# Top_Level.net
KiCad netlist of a schematic drawn in Altium Designer
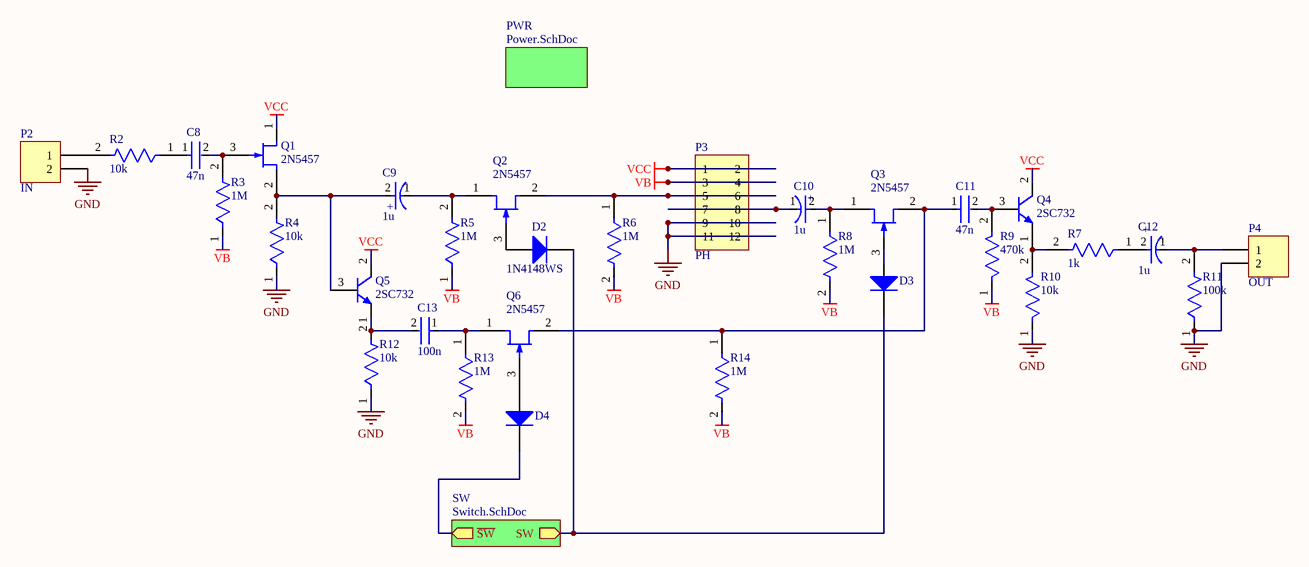
[diagram p0: Top_Level.SchDoc]

(export (version "E")
  (design (tool "Eeschema 10.0.6"))
  (components
    (comp (ref "C8")
      (value "47n")
      (footprint "FP-CL10-IPC_A")
      (description "Cap Ceramic 1nF 50V C0G ±5% Pad SMD 0603 +125°C T/R")
      (fields (field (name "VOLTAGE") "50V") (field (name "TOLERANCE") "5%"))
      (libsource (lib "Altium Content Vault") (part "b4654b650e69147ec39a6b967a45e02"))
    )
    (comp (ref "C9")
      (value "1u")
      (footprint "FP-TAJA-MFG")
      (description "10uF 16V  ±10% 3Ω 1206  SMD Tantalum Capacitor")
      (fields (field (name "VOLTAGE") "16V") (field (name "TOLERANCE") "10%"))
      (libsource (lib "Altium Content Vault") (part "203bc49f2ac43e59fd269a8c329ed05"))
    )
    (comp (ref "C10")
      (value "1u")
      (footprint "FP-TAJA-MFG")
      (description "10uF 16V  ±10% 3Ω 1206  SMD Tantalum Capacitor")
      (fields (field (name "VOLTAGE") "16V") (field (name "TOLERANCE") "10%"))
      (libsource (lib "Altium Content Vault") (part "203bc49f2ac43e59fd269a8c329ed05"))
    )
    (comp (ref "C11")
      (value "47n")
      (footprint "FP-CL10-IPC_A")
      (description "Cap Ceramic 1nF 50V C0G ±5% Pad SMD 0603 +125°C T/R")
      (fields (field (name "VOLTAGE") "50V") (field (name "TOLERANCE") "5%"))
      (libsource (lib "Altium Content Vault") (part "b4654b650e69147ec39a6b967a45e02"))
    )
    (comp (ref "C12")
      (value "1u")
      (footprint "FP-TAJA-MFG")
      (description "10uF 16V  ±10% 3Ω 1206  SMD Tantalum Capacitor")
      (fields (field (name "VOLTAGE") "16V") (field (name "TOLERANCE") "10%"))
      (libsource (lib "Altium Content Vault") (part "203bc49f2ac43e59fd269a8c329ed05"))
    )
    (comp (ref "C13")
      (value "100n")
      (footprint "FP-CL10-IPC_A")
      (description "Cap Ceramic 1nF 50V C0G ±5% Pad SMD 0603 +125°C T/R")
      (fields (field (name "VOLTAGE") "50V") (field (name "TOLERANCE") "5%"))
      (libsource (lib "Altium Content Vault") (part "b4654b650e69147ec39a6b967a45e02"))
    )
    (comp (ref "D2")
      (value "1N4148WS")
      (footprint "DIOD-SOD323-2-A_V")
      (description "Fast Switching Diode, 75 V, 0.3 A, -65 to 150 degC, 2-Pin SOD323, RoHS, Tape and Reel")
      (libsource (lib "Altium Content Vault") (part "D-AK-2"))
    )
    (comp (ref "D3")
      (value "1N4148WS")
      (footprint "DIOD-SOD323-2-A_V")
      (description "Fast Switching Diode, 75 V, 0.3 A, -65 to 150 degC, 2-Pin SOD323, RoHS, Tape and Reel")
      (libsource (lib "Altium Content Vault") (part "D-AK-2"))
    )
    (comp (ref "D4")
      (value "1N4148WS")
      (footprint "DIOD-SOD323-2-A_V")
      (description "Fast Switching Diode, 75 V, 0.3 A, -65 to 150 degC, 2-Pin SOD323, RoHS, Tape and Reel")
      (libsource (lib "Altium Content Vault") (part "D-AK-2"))
    )
    (comp (ref "P2")
      (value "IN")
      (footprint "HDR1X2")
      (description "Header, 2-Pin")
      (fields (field (name "PUBLISHER") "Altium Limited"))
      (libsource (lib "Miscellaneous Connectors") (part "Header 2"))
    )
    (comp (ref "P3")
      (value "PH")
      (footprint "HDR2X6")
      (description "Header, 6-Pin, Dual row")
      (fields (field (name "PUBLISHER") "Altium Limited"))
      (libsource (lib "Miscellaneous Connectors") (part "Header 6X2"))
    )
    (comp (ref "P4")
      (value "OUT")
      (footprint "HDR1X2")
      (description "Header, 2-Pin")
      (fields (field (name "PUBLISHER") "Altium Limited"))
      (libsource (lib "") (part "Header 2_1"))
    )
    (comp (ref "Q1") (value "2N5457") (footprint "TO-92") (libsource (lib "TH_Symbols") (part "JFET_NPN")))
    (comp (ref "Q2") (value "2N5457") (footprint "TO-92") (libsource (lib "TH_Symbols") (part "JFET_NPN")))
    (comp (ref "Q3") (value "2N5457") (footprint "TO-92") (libsource (lib "TH_Symbols") (part "JFET_NPN")))
    (comp (ref "Q4") (value "2SC732") (footprint "TO-92") (libsource (lib "TH_Symbols") (part "BJT_NPN")))
    (comp (ref "Q5") (value "2SC732") (footprint "TO-92") (libsource (lib "TH_Symbols") (part "BJT_NPN")))
    (comp (ref "Q6") (value "2N5457") (footprint "TO-92") (libsource (lib "TH_Symbols") (part "JFET_NPN")))
    (comp (ref "R2")
      (value "10k")
      (footprint "FP-RT0805-MFG")
      (description "RES SMD 10K OHM 0.1% 1/8W 0805")
      (fields
        (field (name "MANUFACTURER PART NUMBER") "RT0805BRE0710KL")
        (field (name "MANUFACTURER") "Yageo")
      )
      (libsource (lib "Altium Content Vault") (part "1029c3af85768c4190bb7ad29bc67b5"))
    )
    (comp (ref "R3")
      (value "1M")
      (footprint "FP-RT0805-MFG")
      (description "RES SMD 10K OHM 0.1% 1/8W 0805")
      (fields
        (field (name "MANUFACTURER PART NUMBER") "RT0805BRE0710KL")
        (field (name "MANUFACTURER") "Yageo")
      )
      (libsource (lib "Altium Content Vault") (part "1029c3af85768c4190bb7ad29bc67b5"))
    )
    (comp (ref "R4")
      (value "10k")
      (footprint "FP-RT0805-MFG")
      (description "RES SMD 10K OHM 0.1% 1/8W 0805")
      (fields
        (field (name "MANUFACTURER PART NUMBER") "RT0805BRE0710KL")
        (field (name "MANUFACTURER") "Yageo")
      )
      (libsource (lib "Altium Content Vault") (part "1029c3af85768c4190bb7ad29bc67b5"))
    )
    (comp (ref "R5")
      (value "1M")
      (footprint "FP-RT0805-MFG")
      (description "RES SMD 10K OHM 0.1% 1/8W 0805")
      (fields
        (field (name "MANUFACTURER PART NUMBER") "RT0805BRE0710KL")
        (field (name "MANUFACTURER") "Yageo")
      )
      (libsource (lib "Altium Content Vault") (part "1029c3af85768c4190bb7ad29bc67b5"))
    )
    (comp (ref "R6")
      (value "1M")
      (footprint "FP-RT0805-MFG")
      (description "RES SMD 10K OHM 0.1% 1/8W 0805")
      (fields
        (field (name "MANUFACTURER PART NUMBER") "RT0805BRE0710KL")
        (field (name "MANUFACTURER") "Yageo")
      )
      (libsource (lib "Altium Content Vault") (part "1029c3af85768c4190bb7ad29bc67b5"))
    )
    (comp (ref "R7")
      (value "1k")
      (footprint "FP-RT0805-MFG")
      (description "RES SMD 10K OHM 0.1% 1/8W 0805")
      (fields
        (field (name "MANUFACTURER PART NUMBER") "RT0805BRE0710KL")
        (field (name "MANUFACTURER") "Yageo")
      )
      (libsource (lib "Altium Content Vault") (part "1029c3af85768c4190bb7ad29bc67b5"))
    )
    (comp (ref "R8")
      (value "1M")
      (footprint "FP-RT0805-MFG")
      (description "RES SMD 10K OHM 0.1% 1/8W 0805")
      (fields
        (field (name "MANUFACTURER PART NUMBER") "RT0805BRE0710KL")
        (field (name "MANUFACTURER") "Yageo")
      )
      (libsource (lib "Altium Content Vault") (part "1029c3af85768c4190bb7ad29bc67b5"))
    )
    (comp (ref "R9")
      (value "470k")
      (footprint "FP-RT0805-MFG")
      (description "RES SMD 10K OHM 0.1% 1/8W 0805")
      (fields
        (field (name "MANUFACTURER PART NUMBER") "RT0805BRE0710KL")
        (field (name "MANUFACTURER") "Yageo")
      )
      (libsource (lib "Altium Content Vault") (part "1029c3af85768c4190bb7ad29bc67b5"))
    )
    (comp (ref "R10")
      (value "10k")
      (footprint "FP-RT0805-MFG")
      (description "RES SMD 10K OHM 0.1% 1/8W 0805")
      (fields
        (field (name "MANUFACTURER PART NUMBER") "RT0805BRE0710KL")
        (field (name "MANUFACTURER") "Yageo")
      )
      (libsource (lib "Altium Content Vault") (part "1029c3af85768c4190bb7ad29bc67b5"))
    )
    (comp (ref "R11")
      (value "100k")
      (footprint "FP-RT0805-MFG")
      (description "RES SMD 10K OHM 0.1% 1/8W 0805")
      (fields
        (field (name "MANUFACTURER PART NUMBER") "RT0805BRE0710KL")
        (field (name "MANUFACTURER") "Yageo")
      )
      (libsource (lib "Altium Content Vault") (part "1029c3af85768c4190bb7ad29bc67b5"))
    )
    (comp (ref "R12")
      (value "10k")
      (footprint "FP-RT0805-MFG")
      (description "RES SMD 10K OHM 0.1% 1/8W 0805")
      (fields
        (field (name "MANUFACTURER PART NUMBER") "RT0805BRE0710KL")
        (field (name "MANUFACTURER") "Yageo")
      )
      (libsource (lib "Altium Content Vault") (part "1029c3af85768c4190bb7ad29bc67b5"))
    )
    (comp (ref "R13")
      (value "1M")
      (footprint "FP-RT0805-MFG")
      (description "RES SMD 10K OHM 0.1% 1/8W 0805")
      (fields
        (field (name "MANUFACTURER PART NUMBER") "RT0805BRE0710KL")
        (field (name "MANUFACTURER") "Yageo")
      )
      (libsource (lib "Altium Content Vault") (part "1029c3af85768c4190bb7ad29bc67b5"))
    )
    (comp (ref "R14")
      (value "1M")
      (footprint "FP-RT0805-MFG")
      (description "RES SMD 10K OHM 0.1% 1/8W 0805")
      (fields
        (field (name "MANUFACTURER PART NUMBER") "RT0805BRE0710KL")
        (field (name "MANUFACTURER") "Yageo")
      )
      (libsource (lib "Altium Content Vault") (part "1029c3af85768c4190bb7ad29bc67b5"))
    )
  )
  (nets
    (net (code "1") (name "/SW") (class "Default")
      (node (ref "D2") (pin "2") (pinfunction "K_2") (pintype "passive"))
      (node (ref "D3") (pin "2") (pinfunction "K_2") (pintype "passive"))
    )
    (net (code "2") (name "/~{SW}") (class "Default")
      (node (ref "D4") (pin "2") (pinfunction "K_2") (pintype "passive"))
    )
    (net (code "3") (name "GND") (class "Default")
      (node (ref "P2") (pin "2") (pinfunction "2_2") (pintype "passive"))
      (node (ref "P3") (pin "10") (pinfunction "10_10") (pintype "passive"))
      (node (ref "P3") (pin "11") (pinfunction "11_11") (pintype "passive"))
      (node (ref "P3") (pin "12") (pinfunction "12_12") (pintype "passive"))
      (node (ref "P3") (pin "9") (pinfunction "9_9") (pintype "passive"))
      (node (ref "P4") (pin "2") (pinfunction "2_2") (pintype "passive"))
      (node (ref "R10") (pin "1") (pinfunction "1_1") (pintype "passive"))
      (node (ref "R11") (pin "1") (pinfunction "1_1") (pintype "passive"))
      (node (ref "R12") (pin "1") (pinfunction "1_1") (pintype "passive"))
      (node (ref "R4") (pin "1") (pinfunction "1_1") (pintype "passive"))
    )
    (net (code "4") (name "Net-(C8-Pad1)") (class "Default")
      (node (ref "C8") (pin "1") (pinfunction "1_1") (pintype "passive"))
      (node (ref "R2") (pin "1") (pinfunction "1_1") (pintype "passive"))
    )
    (net (code "5") (name "Net-(C9-A)") (class "Default")
      (node (ref "C9") (pin "2") (pinfunction "A_2") (pintype "passive"))
      (node (ref "Q1") (pin "2") (pinfunction "S_2") (pintype "passive"))
      (node (ref "Q5") (pin "3") (pinfunction "B_3") (pintype "passive"))
      (node (ref "R4") (pin "2") (pinfunction "2_2") (pintype "passive"))
    )
    (net (code "6") (name "Net-(C9-C)") (class "Default")
      (node (ref "C9") (pin "1") (pinfunction "C_1") (pintype "passive"))
      (node (ref "Q2") (pin "1") (pinfunction "D_1") (pintype "passive"))
      (node (ref "R5") (pin "2") (pinfunction "2_2") (pintype "passive"))
    )
    (net (code "7") (name "Net-(C10-A)") (class "Default")
      (node (ref "C10") (pin "2") (pinfunction "A_2") (pintype "passive"))
      (node (ref "Q3") (pin "1") (pinfunction "D_1") (pintype "passive"))
      (node (ref "R8") (pin "1") (pinfunction "1_1") (pintype "passive"))
    )
    (net (code "8") (name "Net-(C10-C)") (class "Default")
      (node (ref "C10") (pin "1") (pinfunction "C_1") (pintype "passive"))
      (node (ref "P3") (pin "7") (pinfunction "7_7") (pintype "passive"))
      (node (ref "P3") (pin "8") (pinfunction "8_8") (pintype "passive"))
    )
    (net (code "9") (name "Net-(C12-A)") (class "Default")
      (node (ref "C12") (pin "2") (pinfunction "A_2") (pintype "passive"))
      (node (ref "R7") (pin "1") (pinfunction "1_1") (pintype "passive"))
    )
    (net (code "10") (name "Net-(C12-C)") (class "Default")
      (node (ref "C12") (pin "1") (pinfunction "C_1") (pintype "passive"))
      (node (ref "P4") (pin "1") (pinfunction "1_1") (pintype "passive"))
      (node (ref "R11") (pin "2") (pinfunction "2_2") (pintype "passive"))
    )
    (net (code "11") (name "Net-(D2-A)") (class "Default")
      (node (ref "D2") (pin "1") (pinfunction "A_1") (pintype "passive"))
      (node (ref "Q2") (pin "3") (pinfunction "G_3") (pintype "passive"))
    )
    (net (code "12") (name "Net-(D3-A)") (class "Default")
      (node (ref "D3") (pin "1") (pinfunction "A_1") (pintype "passive"))
      (node (ref "Q3") (pin "3") (pinfunction "G_3") (pintype "passive"))
    )
    (net (code "13") (name "Net-(D4-A)") (class "Default")
      (node (ref "D4") (pin "1") (pinfunction "A_1") (pintype "passive"))
      (node (ref "Q6") (pin "3") (pinfunction "G_3") (pintype "passive"))
    )
    (net (code "14") (name "Net-(P2-Pad1)") (class "Default")
      (node (ref "P2") (pin "1") (pinfunction "1_1") (pintype "passive"))
      (node (ref "R2") (pin "2") (pinfunction "2_2") (pintype "passive"))
    )
    (net (code "15") (name "Net-(Q1-G)") (class "Default")
      (node (ref "C8") (pin "2") (pinfunction "2_2") (pintype "passive"))
      (node (ref "Q1") (pin "3") (pinfunction "G_3") (pintype "passive"))
      (node (ref "R3") (pin "2") (pinfunction "2_2") (pintype "passive"))
    )
    (net (code "16") (name "Net-(Q2-S)") (class "Default")
      (node (ref "P3") (pin "5") (pinfunction "5_5") (pintype "passive"))
      (node (ref "P3") (pin "6") (pinfunction "6_6") (pintype "passive"))
      (node (ref "Q2") (pin "2") (pinfunction "S_2") (pintype "passive"))
      (node (ref "R6") (pin "1") (pinfunction "1_1") (pintype "passive"))
    )
    (net (code "17") (name "Net-(Q3-S)") (class "Default")
      (node (ref "C11") (pin "1") (pinfunction "1_1") (pintype "passive"))
      (node (ref "Q3") (pin "2") (pinfunction "S_2") (pintype "passive"))
      (node (ref "Q6") (pin "2") (pinfunction "S_2") (pintype "passive"))
      (node (ref "R14") (pin "1") (pinfunction "1_1") (pintype "passive"))
    )
    (net (code "18") (name "Net-(Q4-B)") (class "Default")
      (node (ref "C11") (pin "2") (pinfunction "2_2") (pintype "passive"))
      (node (ref "Q4") (pin "3") (pinfunction "B_3") (pintype "passive"))
      (node (ref "R9") (pin "2") (pinfunction "2_2") (pintype "passive"))
    )
    (net (code "19") (name "Net-(Q4-E)") (class "Default")
      (node (ref "Q4") (pin "1") (pinfunction "E_1") (pintype "passive"))
      (node (ref "R10") (pin "2") (pinfunction "2_2") (pintype "passive"))
      (node (ref "R7") (pin "2") (pinfunction "2_2") (pintype "passive"))
    )
    (net (code "20") (name "Net-(Q5-E)") (class "Default")
      (node (ref "C13") (pin "2") (pinfunction "2_2") (pintype "passive"))
      (node (ref "Q5") (pin "1") (pinfunction "E_1") (pintype "passive"))
      (node (ref "R12") (pin "2") (pinfunction "2_2") (pintype "passive"))
    )
    (net (code "21") (name "Net-(Q6-D)") (class "Default")
      (node (ref "C13") (pin "1") (pinfunction "1_1") (pintype "passive"))
      (node (ref "Q6") (pin "1") (pinfunction "D_1") (pintype "passive"))
      (node (ref "R13") (pin "1") (pinfunction "1_1") (pintype "passive"))
    )
    (net (code "22") (name "VB") (class "Default")
      (node (ref "P3") (pin "3") (pinfunction "3_3") (pintype "passive"))
      (node (ref "P3") (pin "4") (pinfunction "4_4") (pintype "passive"))
      (node (ref "R13") (pin "2") (pinfunction "2_2") (pintype "passive"))
      (node (ref "R14") (pin "2") (pinfunction "2_2") (pintype "passive"))
      (node (ref "R3") (pin "1") (pinfunction "1_1") (pintype "passive"))
      (node (ref "R5") (pin "1") (pinfunction "1_1") (pintype "passive"))
      (node (ref "R6") (pin "2") (pinfunction "2_2") (pintype "passive"))
      (node (ref "R8") (pin "2") (pinfunction "2_2") (pintype "passive"))
      (node (ref "R9") (pin "1") (pinfunction "1_1") (pintype "passive"))
    )
    (net (code "23") (name "VCC") (class "Default")
      (node (ref "P3") (pin "1") (pinfunction "1_1") (pintype "passive"))
      (node (ref "P3") (pin "2") (pinfunction "2_2") (pintype "passive"))
      (node (ref "Q1") (pin "1") (pinfunction "D_1") (pintype "passive"))
      (node (ref "Q4") (pin "2") (pinfunction "C_2") (pintype "passive"))
      (node (ref "Q5") (pin "2") (pinfunction "C_2") (pintype "passive"))
    )
  )
)
